# ardustatversion7.net
KiCad netlist of a schematic drawn in EAGLE
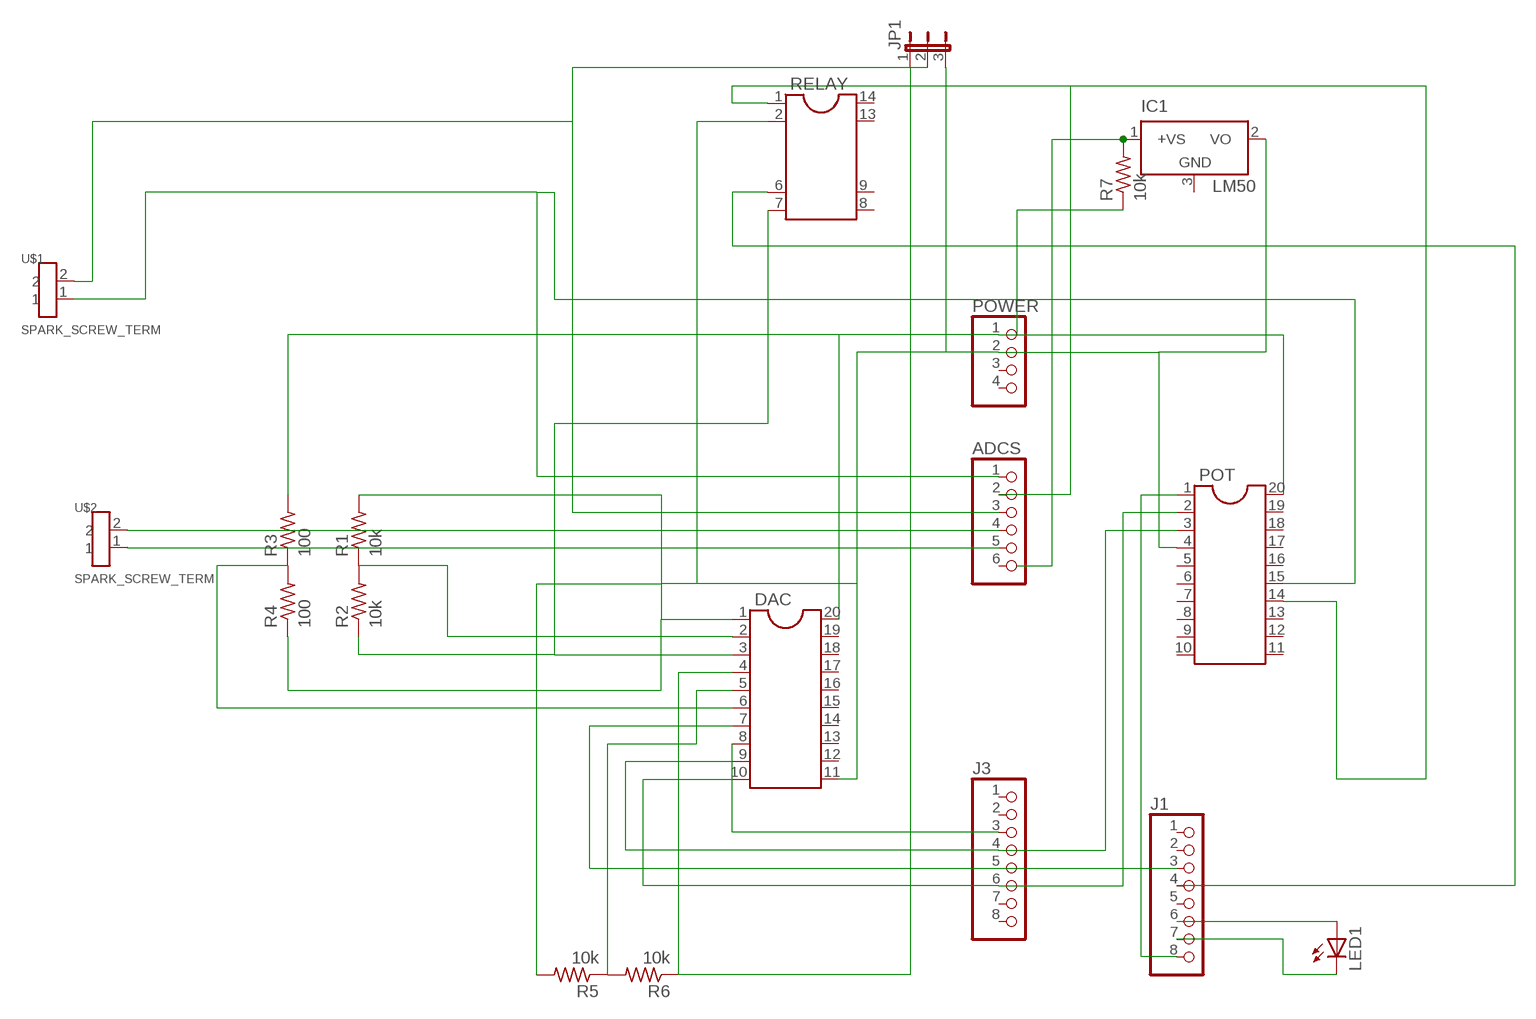
[diagram p0: schematic, sheet 1]

(export (version "E")
  (design (tool "Eeschema 10.0.6"))
  (components
    (comp (ref "ADCS")
      (value "PINHD-1X6")
      (footprint "eagle-import:1X06")
      (libsource (lib "eagle-import") (part "PINHD-1X6"))
    )
    (comp (ref "DAC")
      (value "DIL20S")
      (footprint "eagle-import:SOCKED-20")
      (libsource (lib "eagle-import") (part "DIL20S"))
    )
    (comp (ref "IC1")
      (value "LM50")
      (footprint "eagle-import:SOT23")
      (libsource (lib "eagle-import") (part "LM50"))
    )
    (comp (ref "J1")
      (value "PINHD-1X8")
      (footprint "eagle-import:1X08")
      (libsource (lib "eagle-import") (part "PINHD-1X8"))
    )
    (comp (ref "J3")
      (value "PINHD-1X8")
      (footprint "eagle-import:1X08")
      (libsource (lib "eagle-import") (part "PINHD-1X8"))
    )
    (comp (ref "JP1")
      (value "JP2E")
      (footprint "eagle-import:JP2")
      (libsource (lib "eagle-import") (part "JP2E"))
    )
    (comp (ref "LED1")
      (value "LED5MM")
      (footprint "eagle-import:LED5MM")
      (libsource (lib "eagle-import") (part "LED5MM"))
    )
    (comp (ref "POT")
      (value "DIL20S")
      (footprint "eagle-import:SOCKED-20")
      (libsource (lib "eagle-import") (part "DIL20S"))
    )
    (comp (ref "POWER")
      (value "PINHD-1X4")
      (footprint "eagle-import:1X04")
      (libsource (lib "eagle-import") (part "PINHD-1X4"))
    )
    (comp (ref "R1")
      (value "10k")
      (footprint "eagle-import:0207_12")
      (libsource (lib "eagle-import") (part "R-US_0207/12"))
    )
    (comp (ref "R2")
      (value "10k")
      (footprint "eagle-import:0207_12")
      (libsource (lib "eagle-import") (part "R-US_0207/12"))
    )
    (comp (ref "R3")
      (value "100")
      (footprint "eagle-import:0207_12")
      (libsource (lib "eagle-import") (part "R-US_0207/12"))
    )
    (comp (ref "R4")
      (value "100")
      (footprint "eagle-import:0207_12")
      (libsource (lib "eagle-import") (part "R-US_0207/12"))
    )
    (comp (ref "R5")
      (value "10k")
      (footprint "eagle-import:0207_12")
      (libsource (lib "eagle-import") (part "R-US_0207/12"))
    )
    (comp (ref "R6")
      (value "10k")
      (footprint "eagle-import:0207_12")
      (libsource (lib "eagle-import") (part "R-US_0207/12"))
    )
    (comp (ref "R7")
      (value "10k")
      (footprint "eagle-import:0207_12")
      (libsource (lib "eagle-import") (part "R-US_0207/12"))
    )
    (comp (ref "RELAY")
      (value "DIL14/8")
      (footprint "eagle-import:DIL14_8")
      (libsource (lib "eagle-import") (part "DIL14/8"))
    )
    (comp (ref "U$1")
      (value "SPARK_SCREW_TERM")
      (footprint "eagle-import:SPARK_SCREW_TERM")
      (libsource (lib "eagle-import") (part "SPARK_SCREW_TERM"))
    )
    (comp (ref "U$2")
      (value "SPARK_SCREW_TERM")
      (footprint "eagle-import:SPARK_SCREW_TERM")
      (libsource (lib "eagle-import") (part "SPARK_SCREW_TERM"))
    )
  )
  (nets
    (net (code "1") (name "/GND") (class "Default")
      (node (ref "IC1") (pin "3") (pinfunction "GND_3") (pintype "power_in"))
    )
    (net (code "2") (name "Net-(ADCS-Pad1)") (class "Default")
      (node (ref "ADCS") (pin "1") (pinfunction "1_1") (pintype "passive"))
      (node (ref "POT") (pin "15") (pinfunction "15_15") (pintype "passive"))
      (node (ref "U$1") (pin "1") (pinfunction "1_1") (pintype "bidirectional"))
    )
    (net (code "3") (name "Net-(ADCS-Pad2)") (class "Default")
      (node (ref "ADCS") (pin "2") (pinfunction "2_2") (pintype "passive"))
      (node (ref "POT") (pin "14") (pinfunction "14_14") (pintype "passive"))
      (node (ref "RELAY") (pin "1") (pinfunction "1_1") (pintype "passive"))
    )
    (net (code "4") (name "Net-(ADCS-Pad3)") (class "Default")
      (node (ref "ADCS") (pin "3") (pinfunction "3_3") (pintype "passive"))
      (node (ref "JP1") (pin "2") (pinfunction "2_2") (pintype "passive"))
      (node (ref "U$1") (pin "2") (pinfunction "2_2") (pintype "bidirectional"))
    )
    (net (code "5") (name "Net-(ADCS-Pad4)") (class "Default")
      (node (ref "ADCS") (pin "4") (pinfunction "4_4") (pintype "passive"))
      (node (ref "U$2") (pin "2") (pinfunction "2_2") (pintype "bidirectional"))
    )
    (net (code "6") (name "Net-(ADCS-Pad5)") (class "Default")
      (node (ref "ADCS") (pin "5") (pinfunction "5_5") (pintype "passive"))
      (node (ref "U$2") (pin "1") (pinfunction "1_1") (pintype "bidirectional"))
    )
    (net (code "7") (name "Net-(DAC-Pad2)") (class "Default")
      (node (ref "DAC") (pin "2") (pinfunction "2_2") (pintype "passive"))
      (node (ref "R1") (pin "1") (pinfunction "1_1") (pintype "passive"))
      (node (ref "R2") (pin "2") (pinfunction "2_2") (pintype "passive"))
    )
    (net (code "8") (name "Net-(DAC-Pad3)") (class "Default")
      (node (ref "DAC") (pin "3") (pinfunction "3_3") (pintype "passive"))
      (node (ref "R2") (pin "1") (pinfunction "1_1") (pintype "passive"))
      (node (ref "RELAY") (pin "7") (pinfunction "7_7") (pintype "passive"))
    )
    (net (code "9") (name "Net-(DAC-Pad4)") (class "Default")
      (node (ref "DAC") (pin "4") (pinfunction "4_4") (pintype "passive"))
      (node (ref "JP1") (pin "1") (pinfunction "1_1") (pintype "passive"))
      (node (ref "R6") (pin "1") (pinfunction "1_1") (pintype "passive"))
    )
    (net (code "10") (name "Net-(DAC-Pad5)") (class "Default")
      (node (ref "DAC") (pin "5") (pinfunction "5_5") (pintype "passive"))
      (node (ref "R5") (pin "1") (pinfunction "1_1") (pintype "passive"))
      (node (ref "R6") (pin "2") (pinfunction "2_2") (pintype "passive"))
    )
    (net (code "11") (name "Net-(DAC-Pad6)") (class "Default")
      (node (ref "DAC") (pin "6") (pinfunction "6_6") (pintype "passive"))
      (node (ref "R3") (pin "1") (pinfunction "1_1") (pintype "passive"))
      (node (ref "R4") (pin "2") (pinfunction "2_2") (pintype "passive"))
    )
    (net (code "12") (name "Net-(DAC-Pad7)") (class "Default")
      (node (ref "DAC") (pin "7") (pinfunction "7_7") (pintype "passive"))
      (node (ref "J1") (pin "3") (pinfunction "3_3") (pintype "passive"))
    )
    (net (code "13") (name "Net-(DAC-Pad8)") (class "Default")
      (node (ref "DAC") (pin "8") (pinfunction "8_8") (pintype "passive"))
      (node (ref "J3") (pin "3") (pinfunction "3_3") (pintype "passive"))
    )
    (net (code "14") (name "Net-(DAC-Pad9)") (class "Default")
      (node (ref "DAC") (pin "9") (pinfunction "9_9") (pintype "passive"))
      (node (ref "J3") (pin "4") (pinfunction "4_4") (pintype "passive"))
      (node (ref "POT") (pin "3") (pinfunction "3_3") (pintype "passive"))
    )
    (net (code "15") (name "Net-(DAC-Pad10)") (class "Default")
      (node (ref "DAC") (pin "10") (pinfunction "10_10") (pintype "passive"))
      (node (ref "J3") (pin "6") (pinfunction "6_6") (pintype "passive"))
      (node (ref "POT") (pin "2") (pinfunction "2_2") (pintype "passive"))
    )
    (net (code "16") (name "Net-(DAC-Pad20)") (class "Default")
      (node (ref "DAC") (pin "20") (pinfunction "20_20") (pintype "passive"))
      (node (ref "POT") (pin "20") (pinfunction "20_20") (pintype "passive"))
      (node (ref "POWER") (pin "1") (pinfunction "1_1") (pintype "passive"))
      (node (ref "R3") (pin "2") (pinfunction "2_2") (pintype "passive"))
      (node (ref "R7") (pin "1") (pinfunction "1_1") (pintype "passive"))
    )
    (net (code "17") (name "Net-(IC1-+VS)") (class "Default")
      (node (ref "IC1") (pin "1") (pinfunction "+VS_1") (pintype "input"))
      (node (ref "R7") (pin "2") (pinfunction "2_2") (pintype "passive"))
    )
    (net (code "18") (name "Net-(IC1-VO)") (class "Default")
      (node (ref "DAC") (pin "1") (pinfunction "1_1") (pintype "passive"))
      (node (ref "DAC") (pin "11") (pinfunction "11_11") (pintype "passive"))
      (node (ref "IC1") (pin "2") (pinfunction "VO_2") (pintype "input"))
      (node (ref "JP1") (pin "3") (pinfunction "3_3") (pintype "passive"))
      (node (ref "POT") (pin "4") (pinfunction "4_4") (pintype "passive"))
      (node (ref "POWER") (pin "2") (pinfunction "2_2") (pintype "passive"))
      (node (ref "R1") (pin "2") (pinfunction "2_2") (pintype "passive"))
      (node (ref "R4") (pin "1") (pinfunction "1_1") (pintype "passive"))
      (node (ref "R5") (pin "2") (pinfunction "2_2") (pintype "passive"))
      (node (ref "RELAY") (pin "2") (pinfunction "2_2") (pintype "passive"))
    )
    (net (code "19") (name "Net-(J1-Pad4)") (class "Default")
      (node (ref "J1") (pin "4") (pinfunction "4_4") (pintype "passive"))
      (node (ref "RELAY") (pin "6") (pinfunction "6_6") (pintype "passive"))
    )
    (net (code "20") (name "Net-(J1-Pad6)") (class "Default")
      (node (ref "J1") (pin "6") (pinfunction "6_6") (pintype "passive"))
      (node (ref "LED1") (pin "A") (pinfunction "A_A") (pintype "passive"))
    )
    (net (code "21") (name "Net-(J1-Pad8)") (class "Default")
      (node (ref "J1") (pin "8") (pinfunction "8_8") (pintype "passive"))
      (node (ref "POT") (pin "1") (pinfunction "1_1") (pintype "passive"))
    )
    (net (code "22") (name "Net-(LED1-C)") (class "Default")
      (node (ref "J1") (pin "7") (pinfunction "7_7") (pintype "passive"))
      (node (ref "LED1") (pin "K") (pinfunction "C_K") (pintype "passive"))
    )
    (net (code "23") (name "unconnected-(ADCS-Pad6)") (class "Default")
      (node (ref "ADCS") (pin "6") (pinfunction "6_6") (pintype "passive"))
    )
    (net (code "24") (name "unconnected-(DAC-Pad12)") (class "Default")
      (node (ref "DAC") (pin "12") (pinfunction "12_12") (pintype "passive"))
    )
    (net (code "25") (name "unconnected-(DAC-Pad13)") (class "Default")
      (node (ref "DAC") (pin "13") (pinfunction "13_13") (pintype "passive"))
    )
    (net (code "26") (name "unconnected-(DAC-Pad14)") (class "Default")
      (node (ref "DAC") (pin "14") (pinfunction "14_14") (pintype "passive"))
    )
    (net (code "27") (name "unconnected-(DAC-Pad15)") (class "Default")
      (node (ref "DAC") (pin "15") (pinfunction "15_15") (pintype "passive"))
    )
    (net (code "28") (name "unconnected-(DAC-Pad16)") (class "Default")
      (node (ref "DAC") (pin "16") (pinfunction "16_16") (pintype "passive"))
    )
    (net (code "29") (name "unconnected-(DAC-Pad17)") (class "Default")
      (node (ref "DAC") (pin "17") (pinfunction "17_17") (pintype "passive"))
    )
    (net (code "30") (name "unconnected-(DAC-Pad18)") (class "Default")
      (node (ref "DAC") (pin "18") (pinfunction "18_18") (pintype "passive"))
    )
    (net (code "31") (name "unconnected-(DAC-Pad19)") (class "Default")
      (node (ref "DAC") (pin "19") (pinfunction "19_19") (pintype "passive"))
    )
    (net (code "32") (name "unconnected-(J1-Pad1)") (class "Default")
      (node (ref "J1") (pin "1") (pinfunction "1_1") (pintype "passive"))
    )
    (net (code "33") (name "unconnected-(J1-Pad2)") (class "Default")
      (node (ref "J1") (pin "2") (pinfunction "2_2") (pintype "passive"))
    )
    (net (code "34") (name "unconnected-(J1-Pad5)") (class "Default")
      (node (ref "J1") (pin "5") (pinfunction "5_5") (pintype "passive"))
    )
    (net (code "35") (name "unconnected-(J3-Pad1)") (class "Default")
      (node (ref "J3") (pin "1") (pinfunction "1_1") (pintype "passive"))
    )
    (net (code "36") (name "unconnected-(J3-Pad2)") (class "Default")
      (node (ref "J3") (pin "2") (pinfunction "2_2") (pintype "passive"))
    )
    (net (code "37") (name "unconnected-(J3-Pad5)") (class "Default")
      (node (ref "J3") (pin "5") (pinfunction "5_5") (pintype "passive"))
    )
    (net (code "38") (name "unconnected-(J3-Pad7)") (class "Default")
      (node (ref "J3") (pin "7") (pinfunction "7_7") (pintype "passive"))
    )
    (net (code "39") (name "unconnected-(J3-Pad8)") (class "Default")
      (node (ref "J3") (pin "8") (pinfunction "8_8") (pintype "passive"))
    )
    (net (code "40") (name "unconnected-(POT-Pad5)") (class "Default")
      (node (ref "POT") (pin "5") (pinfunction "5_5") (pintype "passive"))
    )
    (net (code "41") (name "unconnected-(POT-Pad6)") (class "Default")
      (node (ref "POT") (pin "6") (pinfunction "6_6") (pintype "passive"))
    )
    (net (code "42") (name "unconnected-(POT-Pad7)") (class "Default")
      (node (ref "POT") (pin "7") (pinfunction "7_7") (pintype "passive"))
    )
    (net (code "43") (name "unconnected-(POT-Pad8)") (class "Default")
      (node (ref "POT") (pin "8") (pinfunction "8_8") (pintype "passive"))
    )
    (net (code "44") (name "unconnected-(POT-Pad9)") (class "Default")
      (node (ref "POT") (pin "9") (pinfunction "9_9") (pintype "passive"))
    )
    (net (code "45") (name "unconnected-(POT-Pad10)") (class "Default")
      (node (ref "POT") (pin "10") (pinfunction "10_10") (pintype "passive"))
    )
    (net (code "46") (name "unconnected-(POT-Pad11)") (class "Default")
      (node (ref "POT") (pin "11") (pinfunction "11_11") (pintype "passive"))
    )
    (net (code "47") (name "unconnected-(POT-Pad12)") (class "Default")
      (node (ref "POT") (pin "12") (pinfunction "12_12") (pintype "passive"))
    )
    (net (code "48") (name "unconnected-(POT-Pad13)") (class "Default")
      (node (ref "POT") (pin "13") (pinfunction "13_13") (pintype "passive"))
    )
    (net (code "49") (name "unconnected-(POT-Pad16)") (class "Default")
      (node (ref "POT") (pin "16") (pinfunction "16_16") (pintype "passive"))
    )
    (net (code "50") (name "unconnected-(POT-Pad17)") (class "Default")
      (node (ref "POT") (pin "17") (pinfunction "17_17") (pintype "passive"))
    )
    (net (code "51") (name "unconnected-(POT-Pad18)") (class "Default")
      (node (ref "POT") (pin "18") (pinfunction "18_18") (pintype "passive"))
    )
    (net (code "52") (name "unconnected-(POT-Pad19)") (class "Default")
      (node (ref "POT") (pin "19") (pinfunction "19_19") (pintype "passive"))
    )
    (net (code "53") (name "unconnected-(POWER-Pad3)") (class "Default")
      (node (ref "POWER") (pin "3") (pinfunction "3_3") (pintype "passive"))
    )
    (net (code "54") (name "unconnected-(POWER-Pad4)") (class "Default")
      (node (ref "POWER") (pin "4") (pinfunction "4_4") (pintype "passive"))
    )
    (net (code "55") (name "unconnected-(RELAY-Pad8)") (class "Default")
      (node (ref "RELAY") (pin "8") (pinfunction "8_8") (pintype "passive"))
    )
    (net (code "56") (name "unconnected-(RELAY-Pad9)") (class "Default")
      (node (ref "RELAY") (pin "9") (pinfunction "9_9") (pintype "passive"))
    )
    (net (code "57") (name "unconnected-(RELAY-Pad13)") (class "Default")
      (node (ref "RELAY") (pin "13") (pinfunction "13_13") (pintype "passive"))
    )
    (net (code "58") (name "unconnected-(RELAY-Pad14)") (class "Default")
      (node (ref "RELAY") (pin "14") (pinfunction "14_14") (pintype "passive"))
    )
  )
)
